# BMS-SYSTEM-POWER.net
KiCad netlist of a schematic drawn in Altium Designer
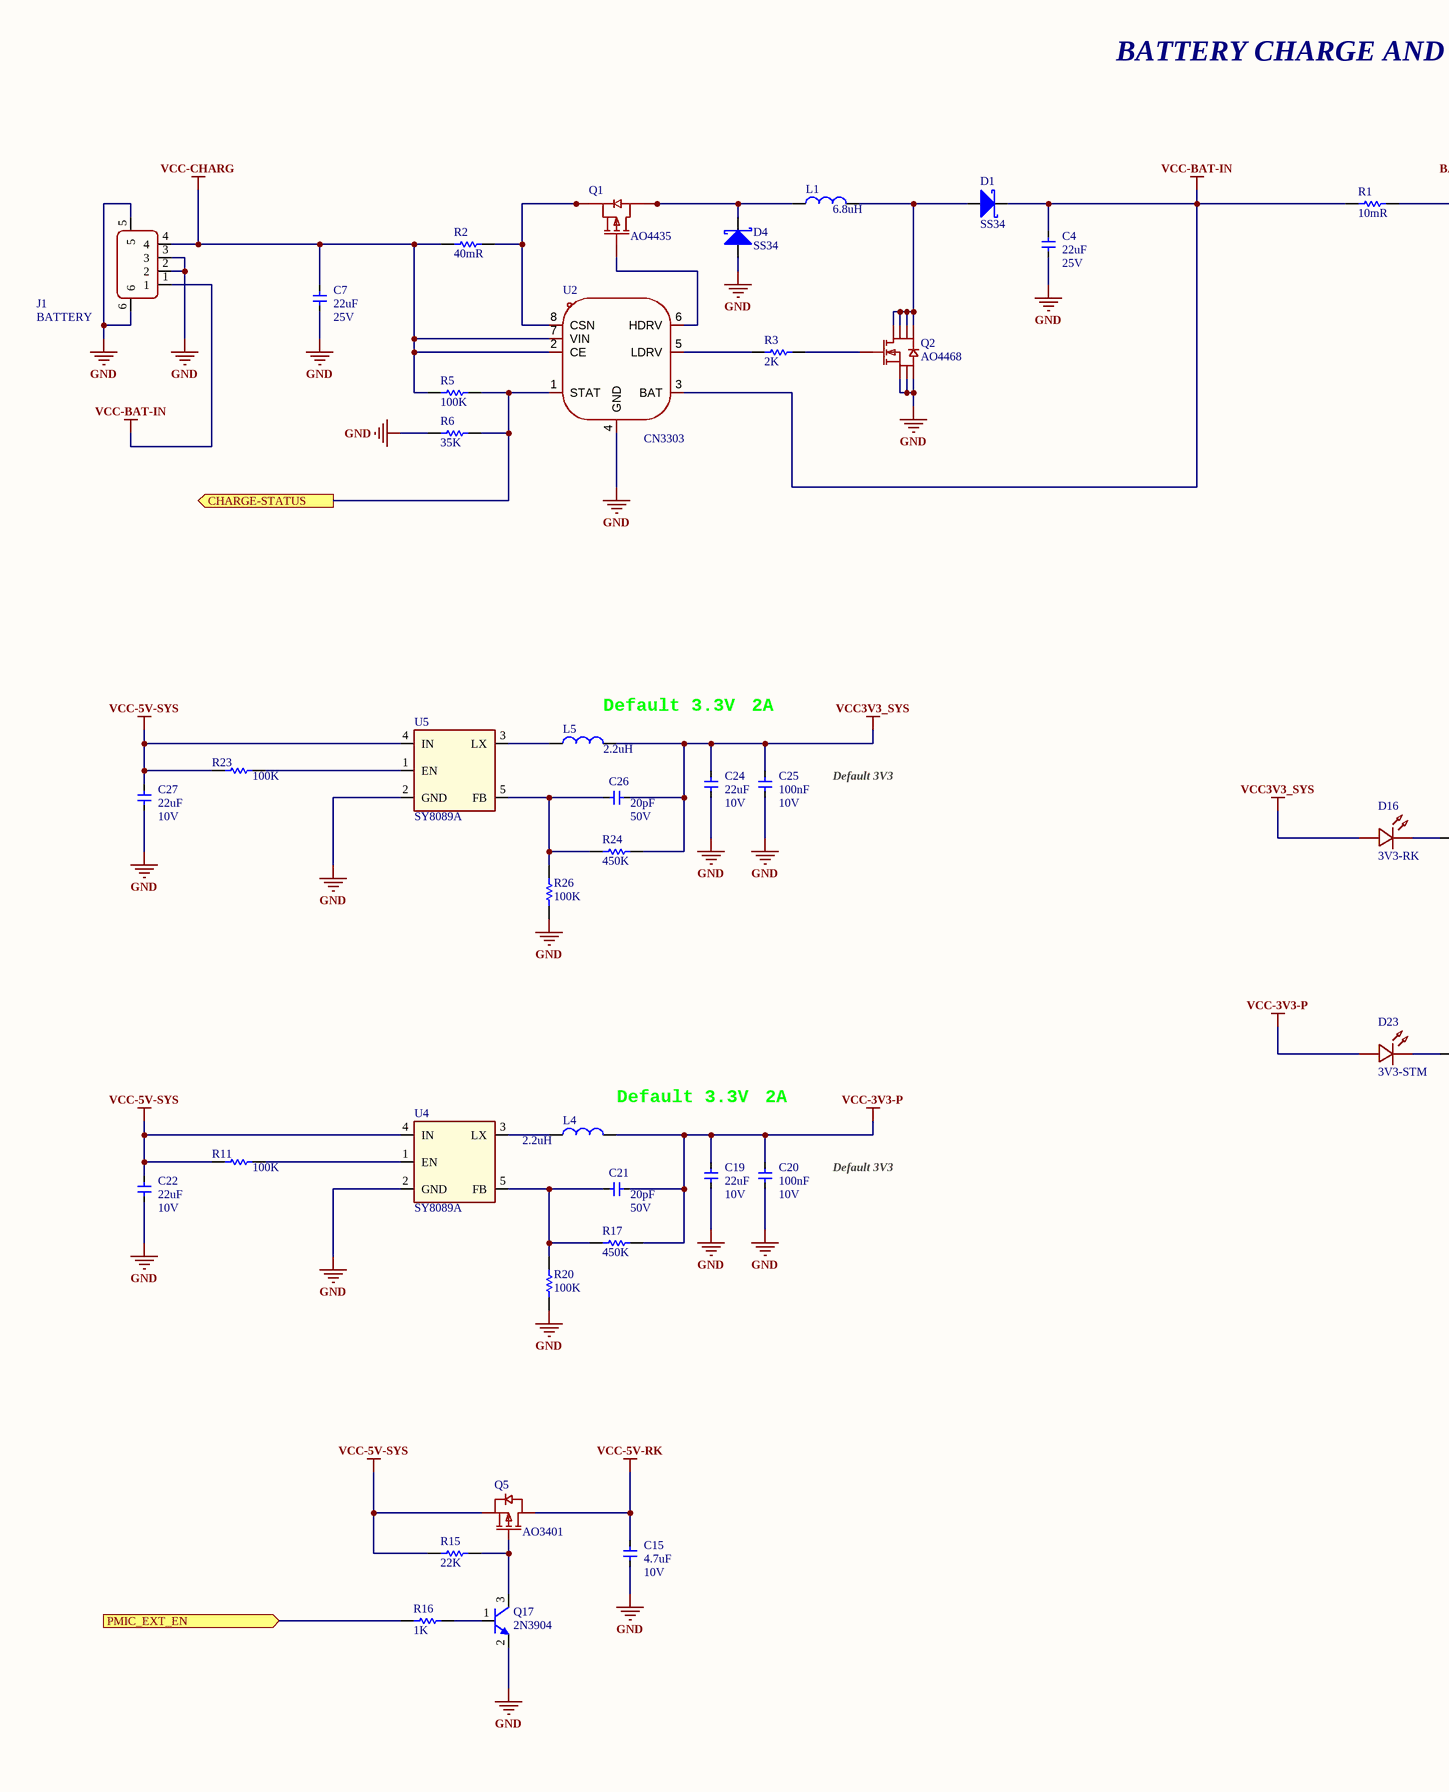
[diagram p0: BMS-SYSTEM-POWER.SchDoc, left]
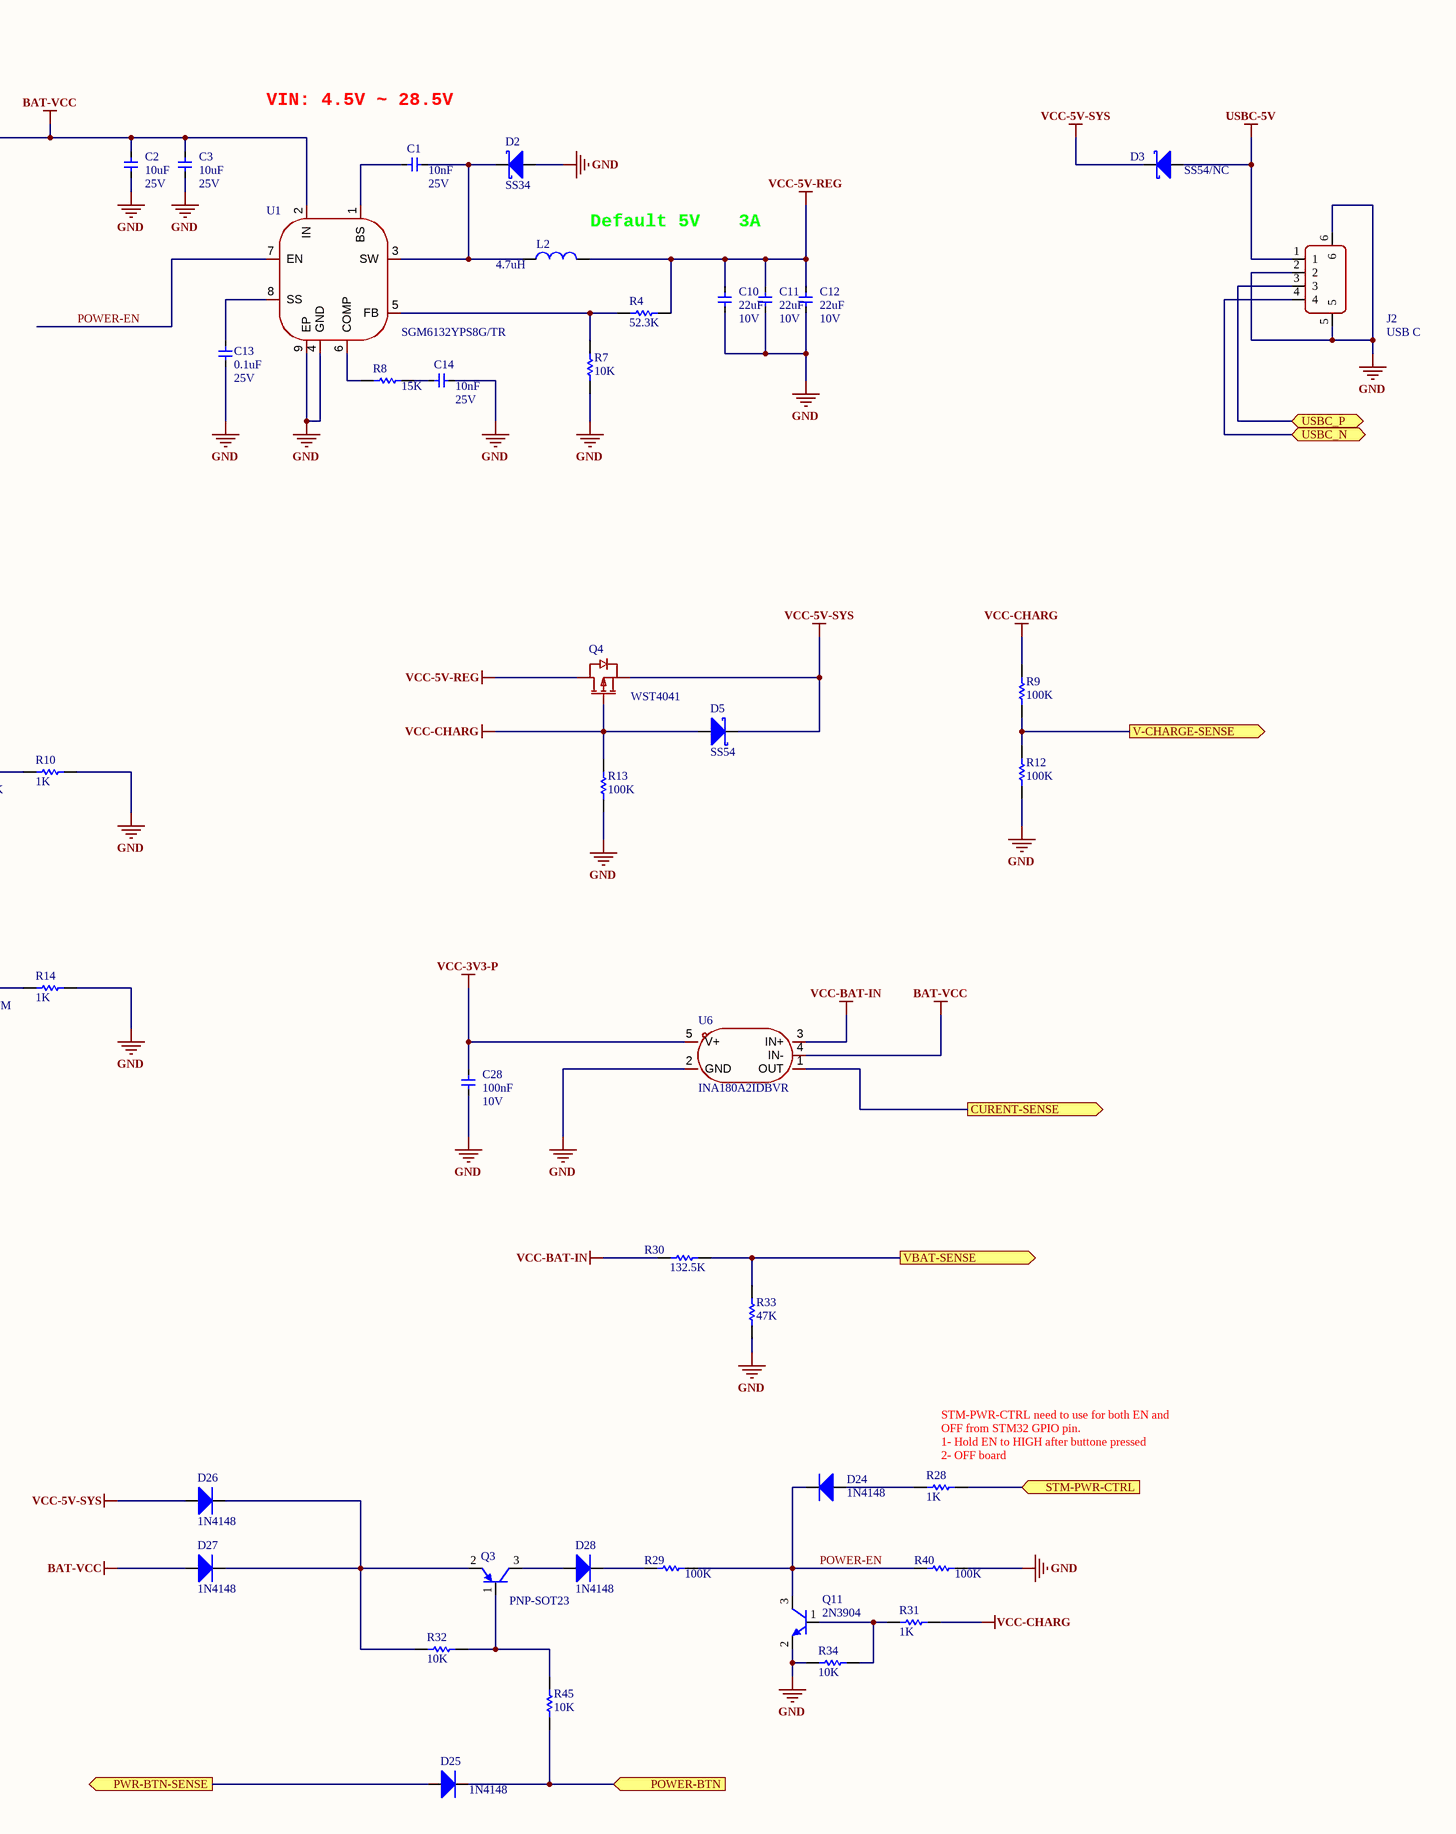
[diagram p1: BMS-SYSTEM-POWER.SchDoc, right]

(export (version "E")
  (design (tool "Eeschema 10.0.6"))
  (components
    (comp (ref "C1")
      (value "10nF")
      (footprint "CAP-0402")
      (fields (field (name "VOLTAGERATE") "25V"))
      (libsource (lib "DesignLibrary") (part "Capacitor-1"))
    )
    (comp (ref "C2")
      (value "10uF")
      (footprint "CAP-0805-S")
      (fields (field (name "VOLTAGERATE") "25V"))
      (libsource (lib "DesignLibrary") (part "Capacitor-1"))
    )
    (comp (ref "C3")
      (value "10uF")
      (footprint "CAP-0805-S")
      (fields (field (name "VOLTAGERATE") "25V"))
      (libsource (lib "DesignLibrary") (part "Capacitor-1"))
    )
    (comp (ref "C4")
      (value "22uF")
      (footprint "C1206")
      (fields (field (name "VOLTAGERATE") "25V"))
      (libsource (lib "DesignLibrary") (part "Capacitor-1"))
    )
    (comp (ref "C7")
      (value "22uF")
      (footprint "C1206")
      (fields (field (name "VOLTAGERATE") "25V"))
      (libsource (lib "DesignLibrary") (part "Capacitor-1"))
    )
    (comp (ref "C10")
      (value "22uF")
      (footprint "CAP-0805-S")
      (fields (field (name "VOLTAGERATE") "10V"))
      (libsource (lib "DesignLibrary") (part "Capacitor-1"))
    )
    (comp (ref "C11")
      (value "22uF")
      (footprint "CAP-0805-S")
      (fields (field (name "VOLTAGERATE") "10V"))
      (libsource (lib "DesignLibrary") (part "Capacitor-1"))
    )
    (comp (ref "C12")
      (value "22uF")
      (footprint "CAP-0805-S")
      (fields (field (name "VOLTAGERATE") "10V"))
      (libsource (lib "DesignLibrary") (part "Capacitor-1"))
    )
    (comp (ref "C13")
      (value "0.1uF")
      (footprint "CAP-0402")
      (fields (field (name "VOLTAGERATE") "25V"))
      (libsource (lib "DesignLibrary") (part "Capacitor-1"))
    )
    (comp (ref "C14")
      (value "10nF")
      (footprint "CAP-0402")
      (fields (field (name "VOLTAGERATE") "25V"))
      (libsource (lib "DesignLibrary") (part "Capacitor-1"))
    )
    (comp (ref "C15")
      (value "4.7uF")
      (footprint "CAP-0603")
      (fields (field (name "VOLTAGERATE") "10V"))
      (libsource (lib "DesignLibrary") (part "Capacitor-1"))
    )
    (comp (ref "C19")
      (value "22uF")
      (footprint "CAP-0603")
      (fields (field (name "VOLTAGERATE") "10V"))
      (libsource (lib "DesignLibrary") (part "Capacitor-1"))
    )
    (comp (ref "C20")
      (value "100nF")
      (footprint "CAP-0402")
      (fields (field (name "VOLTAGERATE") "10V"))
      (libsource (lib "DesignLibrary") (part "Capacitor-1"))
    )
    (comp (ref "C21")
      (value "20pF")
      (footprint "CAP-0402")
      (fields (field (name "VOLTAGERATE") "50V"))
      (libsource (lib "DesignLibrary") (part "Capacitor-1"))
    )
    (comp (ref "C22")
      (value "22uF")
      (footprint "CAP-0603")
      (fields (field (name "VOLTAGERATE") "10V"))
      (libsource (lib "DesignLibrary") (part "Capacitor-1"))
    )
    (comp (ref "C24")
      (value "22uF")
      (footprint "CAP-0603")
      (fields (field (name "VOLTAGERATE") "10V"))
      (libsource (lib "DesignLibrary") (part "Capacitor-1"))
    )
    (comp (ref "C25")
      (value "100nF")
      (footprint "CAP-0402")
      (fields (field (name "VOLTAGERATE") "10V"))
      (libsource (lib "DesignLibrary") (part "Capacitor-1"))
    )
    (comp (ref "C26")
      (value "20pF")
      (footprint "CAP-0402")
      (fields (field (name "VOLTAGERATE") "50V"))
      (libsource (lib "DesignLibrary") (part "Capacitor-1"))
    )
    (comp (ref "C27")
      (value "22uF")
      (footprint "CAP-0603")
      (fields (field (name "VOLTAGERATE") "10V"))
      (libsource (lib "DesignLibrary") (part "Capacitor-1"))
    )
    (comp (ref "C28")
      (value "100nF")
      (footprint "CAP-0402")
      (fields (field (name "VOLTAGERATE") "10V"))
      (libsource (lib "DesignLibrary") (part "Capacitor-1"))
    )
    (comp (ref "D1") (value "SS34") (footprint "SMA") (libsource (lib "DesignLibrary") (part "DIODE-2")))
    (comp (ref "D2") (value "SS34") (footprint "SMA") (libsource (lib "DesignLibrary") (part "DIODE-2")))
    (comp (ref "D3")
      (value "SS54/NC")
      (footprint "SMB_L4.3-W3.6-LS5.4-RD")
      (libsource (lib "DesignLibrary") (part "DIODE-2"))
    )
    (comp (ref "D4") (value "SS34") (footprint "SMA") (libsource (lib "DesignLibrary") (part "DIODE-2")))
    (comp (ref "D5")
      (value "SS54")
      (footprint "SMB_L4.3-W3.6-LS5.4-RD")
      (libsource (lib "DesignLibrary") (part "DIODE-2"))
    )
    (comp (ref "D16")
      (value "3V3-RK")
      (footprint "LED0603-B")
      (libsource (lib "DesignLibrary") (part "LED-SMD"))
    )
    (comp (ref "D23")
      (value "3V3-STM")
      (footprint "LED0603-B")
      (libsource (lib "DesignLibrary") (part "LED-SMD"))
    )
    (comp (ref "D24")
      (value "1N4148")
      (footprint "SOD123")
      (libsource (lib "DesignLibrary") (part "DIODE-1"))
    )
    (comp (ref "D25")
      (value "1N4148")
      (footprint "SOD123")
      (libsource (lib "DesignLibrary") (part "DIODE-1"))
    )
    (comp (ref "D26")
      (value "1N4148")
      (footprint "SOD123")
      (libsource (lib "DesignLibrary") (part "DIODE-1"))
    )
    (comp (ref "D27")
      (value "1N4148")
      (footprint "SOD123")
      (libsource (lib "DesignLibrary") (part "DIODE-1"))
    )
    (comp (ref "D28")
      (value "1N4148")
      (footprint "SOD123")
      (libsource (lib "DesignLibrary") (part "DIODE-1"))
    )
    (comp (ref "J1")
      (value "BATTERY")
      (footprint "CONN-SMD_4P-P2.00_XUNPU_WAFER-PH2.0-4PWB")
      (libsource (lib "DesignLibrary") (part "HDRx4"))
    )
    (comp (ref "J2")
      (value "USB C")
      (footprint "CONN-SMD_4P-P2.00_XUNPU_WAFER-PH2.0-4PWB")
      (libsource (lib "DesignLibrary") (part "HDRx4"))
    )
    (comp (ref "L1")
      (value "6.8uH")
      (footprint "IND-SMD_L7.0-W6.6")
      (description "FXL0630-6R8-M")
      (libsource (lib "DesignLibrary") (part "INDUCTOR-SMD"))
    )
    (comp (ref "L2")
      (value "4.7uH")
      (footprint "IND-SMD_L7.0-W6.6")
      (description "FXL0630-4R7-M")
      (libsource (lib "DesignLibrary") (part "INDUCTOR-SMD"))
    )
    (comp (ref "L4")
      (value "2.2uH")
      (footprint "IND-SMD_L4.4-W4.2")
      (description "FXL0420-2R2-M")
      (libsource (lib "DesignLibrary") (part "INDUCTOR-SMD"))
    )
    (comp (ref "L5")
      (value "2.2uH")
      (footprint "IND-SMD_L4.4-W4.2")
      (description "FXL0420-2R2-M")
      (libsource (lib "DesignLibrary") (part "INDUCTOR-SMD"))
    )
    (comp (ref "Q1")
      (value "AO4435")
      (footprint "SOP-8_L4.9-W3.9-P1.27-LS6.0-BL-1")
      (libsource (lib "DesignLibrary") (part "AO4407A"))
    )
    (comp (ref "Q2")
      (value "AO4468")
      (footprint "SOP-8_L4.9-W3.9-P1.27-LS6.0-BL-1")
      (libsource (lib "DesignLibrary") (part "NCE3018AS"))
    )
    (comp (ref "Q3")
      (value "PNP-SOT23")
      (footprint "SOT23-3D")
      (libsource (lib "DesignLibrary") (part "PNP-SOT23"))
    )
    (comp (ref "Q4")
      (value "WST4041")
      (footprint "SOT23-3D")
      (libsource (lib "DesignLibrary") (part "P-MOS-SOT23"))
    )
    (comp (ref "Q5")
      (value "AO3401")
      (footprint "SOT23-3D")
      (libsource (lib "DesignLibrary") (part "P-MOS-SOT23"))
    )
    (comp (ref "Q11")
      (value "2N3904")
      (footprint "SOT23-3D")
      (libsource (lib "DesignLibrary") (part "NPN-SOT23"))
    )
    (comp (ref "Q17")
      (value "2N3904")
      (footprint "SOT23-3D")
      (libsource (lib "DesignLibrary") (part "NPN-SOT23"))
    )
    (comp (ref "R1")
      (value "10mR")
      (footprint "RES-1206")
      (libsource (lib "DesignLibrary") (part "Resistor-1"))
    )
    (comp (ref "R2") (value "40mR") (footprint "R1210") (libsource (lib "DesignLibrary") (part "Resistor-1")))
    (comp (ref "R3")
      (value "2K")
      (footprint "RES-0402")
      (libsource (lib "DesignLibrary") (part "Resistor-1"))
    )
    (comp (ref "R4")
      (value "52.3K")
      (footprint "RES-0402")
      (libsource (lib "DesignLibrary") (part "Resistor-1"))
    )
    (comp (ref "R5")
      (value "100K")
      (footprint "RES-0402")
      (libsource (lib "DesignLibrary") (part "Resistor-1"))
    )
    (comp (ref "R6")
      (value "35K")
      (footprint "RES-0402")
      (libsource (lib "DesignLibrary") (part "Resistor-1"))
    )
    (comp (ref "R7")
      (value "10K")
      (footprint "RES-0402")
      (libsource (lib "DesignLibrary") (part "Resistor-1"))
    )
    (comp (ref "R8")
      (value "15K")
      (footprint "RES-0402")
      (libsource (lib "DesignLibrary") (part "Resistor-1"))
    )
    (comp (ref "R9")
      (value "100K")
      (footprint "RES-0402")
      (libsource (lib "DesignLibrary") (part "Resistor-1"))
    )
    (comp (ref "R10")
      (value "1K")
      (footprint "RES-0402")
      (libsource (lib "DesignLibrary") (part "Resistor-1"))
    )
    (comp (ref "R11")
      (value "100K")
      (footprint "RES-0402")
      (libsource (lib "DesignLibrary") (part "Resistor-1"))
    )
    (comp (ref "R12")
      (value "100K")
      (footprint "RES-0402")
      (libsource (lib "DesignLibrary") (part "Resistor-1"))
    )
    (comp (ref "R13")
      (value "100K")
      (footprint "RES-0402")
      (libsource (lib "DesignLibrary") (part "Resistor-1"))
    )
    (comp (ref "R14")
      (value "1K")
      (footprint "RES-0402")
      (libsource (lib "DesignLibrary") (part "Resistor-1"))
    )
    (comp (ref "R15")
      (value "22K")
      (footprint "RES-0402")
      (libsource (lib "DesignLibrary") (part "Resistor-1"))
    )
    (comp (ref "R16")
      (value "1K")
      (footprint "RES-0402")
      (libsource (lib "DesignLibrary") (part "Resistor-1"))
    )
    (comp (ref "R17")
      (value "450K")
      (footprint "RES-0402")
      (libsource (lib "DesignLibrary") (part "Resistor-1"))
    )
    (comp (ref "R20")
      (value "100K")
      (footprint "RES-0402")
      (libsource (lib "DesignLibrary") (part "Resistor-1"))
    )
    (comp (ref "R23")
      (value "100K")
      (footprint "RES-0402")
      (libsource (lib "DesignLibrary") (part "Resistor-1"))
    )
    (comp (ref "R24")
      (value "450K")
      (footprint "RES-0402")
      (libsource (lib "DesignLibrary") (part "Resistor-1"))
    )
    (comp (ref "R26")
      (value "100K")
      (footprint "RES-0402")
      (libsource (lib "DesignLibrary") (part "Resistor-1"))
    )
    (comp (ref "R28")
      (value "1K")
      (footprint "RES-0402")
      (libsource (lib "DesignLibrary") (part "Resistor-1"))
    )
    (comp (ref "R29")
      (value "100K")
      (footprint "RES-0402")
      (libsource (lib "DesignLibrary") (part "Resistor-1"))
    )
    (comp (ref "R30")
      (value "132.5K")
      (footprint "RES-0402")
      (libsource (lib "DesignLibrary") (part "Resistor-1"))
    )
    (comp (ref "R31")
      (value "1K")
      (footprint "RES-0402")
      (libsource (lib "DesignLibrary") (part "Resistor-1"))
    )
    (comp (ref "R32")
      (value "10K")
      (footprint "RES-0402")
      (libsource (lib "DesignLibrary") (part "Resistor-1"))
    )
    (comp (ref "R33")
      (value "47K")
      (footprint "RES-0402")
      (libsource (lib "DesignLibrary") (part "Resistor-1"))
    )
    (comp (ref "R34")
      (value "10K")
      (footprint "RES-0402")
      (libsource (lib "DesignLibrary") (part "Resistor-1"))
    )
    (comp (ref "R40")
      (value "100K")
      (footprint "RES-0402")
      (libsource (lib "DesignLibrary") (part "Resistor-1"))
    )
    (comp (ref "R45")
      (value "10K")
      (footprint "RES-0402")
      (libsource (lib "DesignLibrary") (part "Resistor-1"))
    )
    (comp (ref "U1")
      (value "SGM6132YPS8G/TR")
      (footprint "SOIC-8_L4.9-W3.9-P1.27-LS6.0-BL-EP3.4")
      (libsource (lib "DesignLibrary") (part "SGM6132YPS8G/TR"))
    )
    (comp (ref "U2")
      (value "CN3303")
      (footprint "SOP-8_L4.9-W3.9-P1.27-LS6.0-BL-1")
      (libsource (lib "DesignLibrary") (part "CN3303"))
    )
    (comp (ref "U4")
      (value "SY8089A")
      (footprint "SOT5P95B160_300H130")
      (libsource (lib "DesignLibrary") (part "SY8089A_0"))
    )
    (comp (ref "U5")
      (value "SY8089A")
      (footprint "SOT5P95B160_300H130")
      (libsource (lib "DesignLibrary") (part "SY8089A_0"))
    )
    (comp (ref "U6")
      (value "INA180A2IDBVR")
      (footprint "SOT_23_5")
      (libsource (lib "DesignLibrary") (part "INA180A2IDBVR"))
    )
  )
  (nets
    (net (code "1") (name "/CHARGE-STATUS") (class "Default")
      (node (ref "R5") (pin "1") (pintype "passive"))
      (node (ref "R6") (pin "1") (pintype "passive"))
      (node (ref "U2") (pin "1") (pinfunction "STAT_1") (pintype "passive"))
    )
    (net (code "2") (name "/CURENT-SENSE") (class "Default")
      (node (ref "U6") (pin "1") (pinfunction "OUT_1") (pintype "passive"))
    )
    (net (code "3") (name "/PMIC_EXT_EN") (class "Default") (node (ref "R16") (pin "1") (pintype "passive")))
    (net (code "4") (name "/POWER-BTN") (class "Default")
      (node (ref "D25") (pin "2") (pinfunction "K_2") (pintype "passive"))
      (node (ref "R45") (pin "1") (pintype "passive"))
    )
    (net (code "5") (name "/POWER-EN") (class "Default")
      (node (ref "D24") (pin "2") (pinfunction "K_2") (pintype "passive"))
      (node (ref "Q11") (pin "3") (pinfunction "C_3") (pintype "passive"))
      (node (ref "R29") (pin "2") (pintype "passive"))
      (node (ref "R40") (pin "1") (pintype "passive"))
      (node (ref "U1") (pin "7") (pinfunction "EN_7") (pintype "passive"))
    )
    (net (code "6") (name "/PWR-BTN-SENSE") (class "Default")
      (node (ref "D25") (pin "1") (pinfunction "A_1") (pintype "passive"))
    )
    (net (code "7") (name "/STM-PWR-CTRL") (class "Default") (node (ref "R28") (pin "2") (pintype "passive")))
    (net (code "8") (name "/USBC_N") (class "Default")
      (node (ref "J2") (pin "4") (pinfunction "4_4") (pintype "passive"))
    )
    (net (code "9") (name "/USBC_P") (class "Default")
      (node (ref "J2") (pin "3") (pinfunction "3_3") (pintype "passive"))
    )
    (net (code "10") (name "/V-CHARGE-SENSE") (class "Default")
      (node (ref "R12") (pin "2") (pintype "passive"))
      (node (ref "R9") (pin "1") (pintype "passive"))
    )
    (net (code "11") (name "/VBAT-SENSE") (class "Default")
      (node (ref "R30") (pin "2") (pintype "passive"))
      (node (ref "R33") (pin "2") (pintype "passive"))
    )
    (net (code "12") (name "BAT-VCC") (class "Default")
      (node (ref "C2") (pin "2") (pinfunction "2_2") (pintype "passive"))
      (node (ref "C3") (pin "2") (pinfunction "2_2") (pintype "passive"))
      (node (ref "D27") (pin "1") (pinfunction "A_1") (pintype "passive"))
      (node (ref "R1") (pin "2") (pintype "passive"))
      (node (ref "U1") (pin "2") (pinfunction "IN_2") (pintype "passive"))
      (node (ref "U6") (pin "4") (pinfunction "IN-_4") (pintype "passive"))
    )
    (net (code "13") (name "GND") (class "Default")
      (node (ref "C10") (pin "1") (pinfunction "1_1") (pintype "passive"))
      (node (ref "C11") (pin "1") (pinfunction "1_1") (pintype "passive"))
      (node (ref "C12") (pin "1") (pinfunction "1_1") (pintype "passive"))
      (node (ref "C13") (pin "2") (pinfunction "2_2") (pintype "passive"))
      (node (ref "C14") (pin "1") (pinfunction "1_1") (pintype "passive"))
      (node (ref "C15") (pin "1") (pinfunction "1_1") (pintype "passive"))
      (node (ref "C19") (pin "1") (pinfunction "1_1") (pintype "passive"))
      (node (ref "C2") (pin "1") (pinfunction "1_1") (pintype "passive"))
      (node (ref "C20") (pin "1") (pinfunction "1_1") (pintype "passive"))
      (node (ref "C22") (pin "1") (pinfunction "1_1") (pintype "passive"))
      (node (ref "C24") (pin "1") (pinfunction "1_1") (pintype "passive"))
      (node (ref "C25") (pin "1") (pinfunction "1_1") (pintype "passive"))
      (node (ref "C27") (pin "1") (pinfunction "1_1") (pintype "passive"))
      (node (ref "C28") (pin "1") (pinfunction "1_1") (pintype "passive"))
      (node (ref "C3") (pin "1") (pinfunction "1_1") (pintype "passive"))
      (node (ref "C4") (pin "1") (pinfunction "1_1") (pintype "passive"))
      (node (ref "C7") (pin "1") (pinfunction "1_1") (pintype "passive"))
      (node (ref "D2") (pin "1") (pinfunction "A_1") (pintype "passive"))
      (node (ref "D4") (pin "1") (pinfunction "A_1") (pintype "passive"))
      (node (ref "J1") (pin "2") (pinfunction "2_2") (pintype "passive"))
      (node (ref "J1") (pin "3") (pinfunction "3_3") (pintype "passive"))
      (node (ref "J1") (pin "5") (pinfunction "5_5") (pintype "passive"))
      (node (ref "J1") (pin "6") (pinfunction "6_6") (pintype "passive"))
      (node (ref "J2") (pin "2") (pinfunction "2_2") (pintype "passive"))
      (node (ref "J2") (pin "5") (pinfunction "5_5") (pintype "passive"))
      (node (ref "J2") (pin "6") (pinfunction "6_6") (pintype "passive"))
      (node (ref "Q11") (pin "2") (pinfunction "E_2") (pintype "passive"))
      (node (ref "Q17") (pin "2") (pinfunction "E_2") (pintype "passive"))
      (node (ref "Q2") (pin "1") (pinfunction "S_1") (pintype "passive"))
      (node (ref "Q2") (pin "2") (pinfunction "S_2") (pintype "passive"))
      (node (ref "Q2") (pin "3") (pinfunction "S_3") (pintype "passive"))
      (node (ref "R10") (pin "1") (pintype "passive"))
      (node (ref "R12") (pin "1") (pintype "passive"))
      (node (ref "R13") (pin "1") (pintype "passive"))
      (node (ref "R14") (pin "1") (pintype "passive"))
      (node (ref "R20") (pin "2") (pintype "passive"))
      (node (ref "R26") (pin "2") (pintype "passive"))
      (node (ref "R33") (pin "1") (pintype "passive"))
      (node (ref "R34") (pin "2") (pintype "passive"))
      (node (ref "R40") (pin "2") (pintype "passive"))
      (node (ref "R6") (pin "2") (pintype "passive"))
      (node (ref "R7") (pin "1") (pintype "passive"))
      (node (ref "U1") (pin "4") (pinfunction "GND_4") (pintype "passive"))
      (node (ref "U1") (pin "9") (pinfunction "EP_9") (pintype "passive"))
      (node (ref "U2") (pin "4") (pinfunction "GND_4") (pintype "passive"))
      (node (ref "U4") (pin "2") (pinfunction "GND_2") (pintype "passive"))
      (node (ref "U5") (pin "2") (pinfunction "GND_2") (pintype "passive"))
      (node (ref "U6") (pin "2") (pinfunction "GND_2") (pintype "passive"))
    )
    (net (code "14") (name "Net-(C14-Pad2)") (class "Default")
      (node (ref "C14") (pin "2") (pinfunction "2_2") (pintype "passive"))
      (node (ref "R8") (pin "1") (pintype "passive"))
    )
    (net (code "15") (name "Net-(D1-A)") (class "Default")
      (node (ref "D1") (pin "1") (pinfunction "A_1") (pintype "passive"))
      (node (ref "L1") (pin "2") (pinfunction "2_2") (pintype "passive"))
      (node (ref "Q2") (pin "5") (pinfunction "D_5") (pintype "passive"))
      (node (ref "Q2") (pin "6") (pinfunction "D_6") (pintype "passive"))
      (node (ref "Q2") (pin "7") (pinfunction "D_7") (pintype "passive"))
      (node (ref "Q2") (pin "8") (pinfunction "D_8") (pintype "passive"))
    )
    (net (code "16") (name "Net-(D2-K)") (class "Default")
      (node (ref "C1") (pin "1") (pinfunction "1_1") (pintype "passive"))
      (node (ref "D2") (pin "2") (pinfunction "K_2") (pintype "passive"))
      (node (ref "L2") (pin "1") (pinfunction "1_1") (pintype "passive"))
      (node (ref "U1") (pin "3") (pinfunction "SW_3") (pintype "passive"))
    )
    (net (code "17") (name "Net-(D4-K)") (class "Default")
      (node (ref "D4") (pin "2") (pinfunction "K_2") (pintype "passive"))
      (node (ref "L1") (pin "1") (pinfunction "1_1") (pintype "passive"))
      (node (ref "Q1") (pin "5") (pinfunction "D_5") (pintype "passive"))
      (node (ref "Q1") (pin "6") (pinfunction "D_6") (pintype "passive"))
      (node (ref "Q1") (pin "7") (pinfunction "D_7") (pintype "passive"))
      (node (ref "Q1") (pin "8") (pinfunction "D_8") (pintype "passive"))
    )
    (net (code "18") (name "Net-(D16-Pad2)") (class "Default")
      (node (ref "D16") (pin "2") (pinfunction "2_2") (pintype "passive"))
      (node (ref "R10") (pin "2") (pintype "passive"))
    )
    (net (code "19") (name "Net-(D23-Pad2)") (class "Default")
      (node (ref "D23") (pin "2") (pinfunction "2_2") (pintype "passive"))
      (node (ref "R14") (pin "2") (pintype "passive"))
    )
    (net (code "20") (name "Net-(D24-A)") (class "Default")
      (node (ref "D24") (pin "1") (pinfunction "A_1") (pintype "passive"))
      (node (ref "R28") (pin "1") (pintype "passive"))
    )
    (net (code "21") (name "Net-(D26-K)") (class "Default")
      (node (ref "D26") (pin "2") (pinfunction "K_2") (pintype "passive"))
      (node (ref "D27") (pin "2") (pinfunction "K_2") (pintype "passive"))
      (node (ref "Q3") (pin "2") (pinfunction "E_2") (pintype "passive"))
      (node (ref "R32") (pin "2") (pintype "passive"))
    )
    (net (code "22") (name "Net-(D28-A)") (class "Default")
      (node (ref "D28") (pin "1") (pinfunction "A_1") (pintype "passive"))
      (node (ref "Q3") (pin "3") (pinfunction "C_3") (pintype "passive"))
    )
    (net (code "23") (name "Net-(D28-K)") (class "Default")
      (node (ref "D28") (pin "2") (pinfunction "K_2") (pintype "passive"))
      (node (ref "R29") (pin "1") (pintype "passive"))
    )
    (net (code "24") (name "Net-(Q1-G)") (class "Default")
      (node (ref "Q1") (pin "4") (pinfunction "G_4") (pintype "passive"))
      (node (ref "U2") (pin "6") (pinfunction "HDRV_6") (pintype "passive"))
    )
    (net (code "25") (name "Net-(Q2-G)") (class "Default")
      (node (ref "Q2") (pin "4") (pinfunction "G_4") (pintype "passive"))
      (node (ref "R3") (pin "1") (pintype "passive"))
    )
    (net (code "26") (name "Net-(Q3-B)") (class "Default")
      (node (ref "Q3") (pin "1") (pinfunction "B_1") (pintype "passive"))
      (node (ref "R32") (pin "1") (pintype "passive"))
      (node (ref "R45") (pin "2") (pintype "passive"))
    )
    (net (code "27") (name "Net-(Q11-B)") (class "Default")
      (node (ref "Q11") (pin "1") (pinfunction "B_1") (pintype "passive"))
      (node (ref "R31") (pin "1") (pintype "passive"))
      (node (ref "R34") (pin "1") (pintype "passive"))
    )
    (net (code "28") (name "Net-(Q17-B)") (class "Default")
      (node (ref "Q17") (pin "1") (pinfunction "B_1") (pintype "passive"))
      (node (ref "R16") (pin "2") (pintype "passive"))
    )
    (net (code "29") (name "Net-(Q17-C)") (class "Default")
      (node (ref "Q17") (pin "3") (pinfunction "C_3") (pintype "passive"))
      (node (ref "Q5") (pin "1") (pinfunction "G_1") (pintype "passive"))
      (node (ref "R15") (pin "2") (pintype "passive"))
    )
    (net (code "30") (name "Net-(U1-BS)") (class "Default")
      (node (ref "C1") (pin "2") (pinfunction "2_2") (pintype "passive"))
      (node (ref "U1") (pin "1") (pinfunction "BS_1") (pintype "passive"))
    )
    (net (code "31") (name "Net-(U1-COMP)") (class "Default")
      (node (ref "R8") (pin "2") (pintype "passive"))
      (node (ref "U1") (pin "6") (pinfunction "COMP_6") (pintype "passive"))
    )
    (net (code "32") (name "Net-(U1-FB)") (class "Default")
      (node (ref "R4") (pin "1") (pintype "passive"))
      (node (ref "R7") (pin "2") (pintype "passive"))
      (node (ref "U1") (pin "5") (pinfunction "FB_5") (pintype "passive"))
    )
    (net (code "33") (name "Net-(U1-SS)") (class "Default")
      (node (ref "C13") (pin "1") (pinfunction "1_1") (pintype "passive"))
      (node (ref "U1") (pin "8") (pinfunction "SS_8") (pintype "passive"))
    )
    (net (code "34") (name "Net-(U2-CSN)") (class "Default")
      (node (ref "Q1") (pin "1") (pinfunction "S_1") (pintype "passive"))
      (node (ref "Q1") (pin "2") (pinfunction "S_2") (pintype "passive"))
      (node (ref "Q1") (pin "3") (pinfunction "S_3") (pintype "passive"))
      (node (ref "R2") (pin "2") (pintype "passive"))
      (node (ref "U2") (pin "8") (pinfunction "CSN_8") (pintype "passive"))
    )
    (net (code "35") (name "Net-(U2-LDRV)") (class "Default")
      (node (ref "R3") (pin "2") (pintype "passive"))
      (node (ref "U2") (pin "5") (pinfunction "LDRV_5") (pintype "passive"))
    )
    (net (code "36") (name "Net-(U4-EN)") (class "Default")
      (node (ref "R11") (pin "2") (pintype "passive"))
      (node (ref "U4") (pin "1") (pinfunction "EN_1") (pintype "passive"))
    )
    (net (code "37") (name "Net-(U4-FB)") (class "Default")
      (node (ref "C21") (pin "2") (pinfunction "2_2") (pintype "passive"))
      (node (ref "R17") (pin "2") (pintype "passive"))
      (node (ref "R20") (pin "1") (pintype "passive"))
      (node (ref "U4") (pin "5") (pinfunction "FB_5") (pintype "passive"))
    )
    (net (code "38") (name "Net-(U4-LX)") (class "Default")
      (node (ref "L4") (pin "1") (pinfunction "1_1") (pintype "passive"))
      (node (ref "U4") (pin "3") (pinfunction "LX_3") (pintype "passive"))
    )
    (net (code "39") (name "Net-(U5-EN)") (class "Default")
      (node (ref "R23") (pin "2") (pintype "passive"))
      (node (ref "U5") (pin "1") (pinfunction "EN_1") (pintype "passive"))
    )
    (net (code "40") (name "Net-(U5-FB)") (class "Default")
      (node (ref "C26") (pin "2") (pinfunction "2_2") (pintype "passive"))
      (node (ref "R24") (pin "2") (pintype "passive"))
      (node (ref "R26") (pin "1") (pintype "passive"))
      (node (ref "U5") (pin "5") (pinfunction "FB_5") (pintype "passive"))
    )
    (net (code "41") (name "Net-(U5-LX)") (class "Default")
      (node (ref "L5") (pin "1") (pinfunction "1_1") (pintype "passive"))
      (node (ref "U5") (pin "3") (pinfunction "LX_3") (pintype "passive"))
    )
    (net (code "42") (name "USBC-5V") (class "Default")
      (node (ref "D3") (pin "1") (pinfunction "A_1") (pintype "passive"))
      (node (ref "J2") (pin "1") (pinfunction "1_1") (pintype "passive"))
    )
    (net (code "43") (name "VCC-3V3-P") (class "Default")
      (node (ref "C19") (pin "2") (pinfunction "2_2") (pintype "passive"))
      (node (ref "C20") (pin "2") (pinfunction "2_2") (pintype "passive"))
      (node (ref "C21") (pin "1") (pinfunction "1_1") (pintype "passive"))
      (node (ref "C28") (pin "2") (pinfunction "2_2") (pintype "passive"))
      (node (ref "D23") (pin "1") (pinfunction "1_1") (pintype "passive"))
      (node (ref "L4") (pin "2") (pinfunction "2_2") (pintype "passive"))
      (node (ref "R17") (pin "1") (pintype "passive"))
      (node (ref "U6") (pin "5") (pinfunction "V+_5") (pintype "passive"))
    )
    (net (code "44") (name "VCC-5V-REG") (class "Default")
      (node (ref "C10") (pin "2") (pinfunction "2_2") (pintype "passive"))
      (node (ref "C11") (pin "2") (pinfunction "2_2") (pintype "passive"))
      (node (ref "C12") (pin "2") (pinfunction "2_2") (pintype "passive"))
      (node (ref "L2") (pin "2") (pinfunction "2_2") (pintype "passive"))
      (node (ref "Q4") (pin "3") (pinfunction "D_3") (pintype "passive"))
      (node (ref "R4") (pin "2") (pintype "passive"))
    )
    (net (code "45") (name "VCC-5V-RK") (class "Default")
      (node (ref "C15") (pin "2") (pinfunction "2_2") (pintype "passive"))
      (node (ref "Q5") (pin "3") (pinfunction "D_3") (pintype "passive"))
    )
    (net (code "46") (name "VCC-5V-SYS") (class "Default")
      (node (ref "C22") (pin "2") (pinfunction "2_2") (pintype "passive"))
      (node (ref "C27") (pin "2") (pinfunction "2_2") (pintype "passive"))
      (node (ref "D26") (pin "1") (pinfunction "A_1") (pintype "passive"))
      (node (ref "D3") (pin "2") (pinfunction "K_2") (pintype "passive"))
      (node (ref "D5") (pin "2") (pinfunction "K_2") (pintype "passive"))
      (node (ref "Q4") (pin "2") (pinfunction "S_2") (pintype "passive"))
      (node (ref "Q5") (pin "2") (pinfunction "S_2") (pintype "passive"))
      (node (ref "R11") (pin "1") (pintype "passive"))
      (node (ref "R15") (pin "1") (pintype "passive"))
      (node (ref "R23") (pin "1") (pintype "passive"))
      (node (ref "U4") (pin "4") (pinfunction "IN_4") (pintype "passive"))
      (node (ref "U5") (pin "4") (pinfunction "IN_4") (pintype "passive"))
    )
    (net (code "47") (name "VCC-BAT-IN") (class "Default")
      (node (ref "C4") (pin "2") (pinfunction "2_2") (pintype "passive"))
      (node (ref "D1") (pin "2") (pinfunction "K_2") (pintype "passive"))
      (node (ref "J1") (pin "1") (pinfunction "1_1") (pintype "passive"))
      (node (ref "R1") (pin "1") (pintype "passive"))
      (node (ref "R30") (pin "1") (pintype "passive"))
      (node (ref "U2") (pin "3") (pinfunction "BAT_3") (pintype "passive"))
      (node (ref "U6") (pin "3") (pinfunction "IN+_3") (pintype "passive"))
    )
    (net (code "48") (name "VCC-CHARG") (class "Default")
      (node (ref "C7") (pin "2") (pinfunction "2_2") (pintype "passive"))
      (node (ref "D5") (pin "1") (pinfunction "A_1") (pintype "passive"))
      (node (ref "J1") (pin "4") (pinfunction "4_4") (pintype "passive"))
      (node (ref "Q4") (pin "1") (pinfunction "G_1") (pintype "passive"))
      (node (ref "R13") (pin "2") (pintype "passive"))
      (node (ref "R2") (pin "1") (pintype "passive"))
      (node (ref "R31") (pin "2") (pintype "passive"))
      (node (ref "R5") (pin "2") (pintype "passive"))
      (node (ref "R9") (pin "2") (pintype "passive"))
      (node (ref "U2") (pin "2") (pinfunction "CE_2") (pintype "passive"))
      (node (ref "U2") (pin "7") (pinfunction "VIN_7") (pintype "passive"))
    )
    (net (code "49") (name "VCC3V3_SYS") (class "Default")
      (node (ref "C24") (pin "2") (pinfunction "2_2") (pintype "passive"))
      (node (ref "C25") (pin "2") (pinfunction "2_2") (pintype "passive"))
      (node (ref "C26") (pin "1") (pinfunction "1_1") (pintype "passive"))
      (node (ref "D16") (pin "1") (pinfunction "1_1") (pintype "passive"))
      (node (ref "L5") (pin "2") (pinfunction "2_2") (pintype "passive"))
      (node (ref "R24") (pin "1") (pintype "passive"))
    )
  )
)
